# CATS-FAT-Battery-Interface.net
KiCad netlist of a schematic drawn in Altium Designer
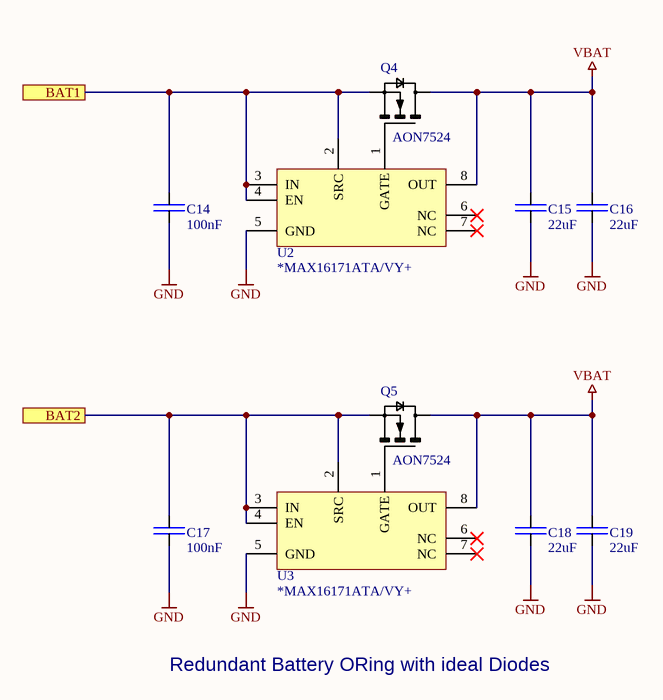
[diagram p0: CATS-FAT-Battery-Interface.SchDoc]

(export (version "E")
  (design (tool "Eeschema 10.0.6"))
  (components
    (comp (ref "C14")
      (value "100nF")
      (footprint "SMD Keramikkondensator 0603")
      (description "SMD Ceramic Capacitor E6")
      (libsource (lib "Ceramic Capacitors-E6") (part "E6 - 100nF"))
    )
    (comp (ref "C15")
      (value "22uF")
      (footprint "SMD Keramikkondensator 0805")
      (description "SMD Ceramic Capacitor E6")
      (libsource (lib "Ceramic Capacitors-E6") (part "E6 - 22uF"))
    )
    (comp (ref "C16")
      (value "22uF")
      (footprint "SMD Keramikkondensator 0805")
      (description "SMD Ceramic Capacitor E6")
      (libsource (lib "Ceramic Capacitors-E6") (part "E6 - 22uF"))
    )
    (comp (ref "C17")
      (value "100nF")
      (footprint "SMD Keramikkondensator 0603")
      (description "SMD Ceramic Capacitor E6")
      (libsource (lib "Ceramic Capacitors-E6") (part "E6 - 100nF"))
    )
    (comp (ref "C18")
      (value "22uF")
      (footprint "SMD Keramikkondensator 0805")
      (description "SMD Ceramic Capacitor E6")
      (libsource (lib "Ceramic Capacitors-E6") (part "E6 - 22uF"))
    )
    (comp (ref "C19")
      (value "22uF")
      (footprint "SMD Keramikkondensator 0805")
      (description "SMD Ceramic Capacitor E6")
      (libsource (lib "Ceramic Capacitors-E6") (part "E6 - 22uF"))
    )
    (comp (ref "Q4")
      (value "AON7524")
      (footprint "SMD MOSFET DFN 3x3 EP")
      (description "N-Channel 30V 25A (Ta), 28A (Tc) 3.1W (Ta), 32W (Tc) Surface Mount 8-DFN (3x3)")
      (libsource (lib "Electronic Switches") (part "AON7524"))
    )
    (comp (ref "Q5")
      (value "AON7524")
      (footprint "SMD MOSFET DFN 3x3 EP")
      (description "N-Channel 30V 25A (Ta), 28A (Tc) 3.1W (Ta), 32W (Tc) Surface Mount 8-DFN (3x3)")
      (libsource (lib "Electronic Switches") (part "AON7524"))
    )
    (comp (ref "U2")
      (value "*MAX16171ATA/VY+")
      (footprint "SMD IC TDFN-8")
      (description "OR Controller N+1 ORing Controller N-Channel 1:1 8-TDFN-CU (2x3)")
      (libsource (lib "Power Management") (part "MAX16171ATA/VY+"))
    )
    (comp (ref "U3")
      (value "*MAX16171ATA/VY+")
      (footprint "SMD IC TDFN-8")
      (description "OR Controller N+1 ORing Controller N-Channel 1:1 8-TDFN-CU (2x3)")
      (libsource (lib "Power Management") (part "MAX16171ATA/VY+"))
    )
  )
  (nets
    (net (code "1") (name "/BAT1") (class "Default")
      (node (ref "C14") (pin "2") (pinfunction "2_2") (pintype "passive"))
      (node (ref "Q4") (pin "S") (pinfunction "S_S") (pintype "passive"))
      (node (ref "U2") (pin "2") (pinfunction "SRC_2") (pintype "passive"))
      (node (ref "U2") (pin "3") (pinfunction "IN_3") (pintype "passive"))
      (node (ref "U2") (pin "4") (pinfunction "EN_4") (pintype "passive"))
    )
    (net (code "2") (name "/BAT2") (class "Default")
      (node (ref "C17") (pin "2") (pinfunction "2_2") (pintype "passive"))
      (node (ref "Q5") (pin "S") (pinfunction "S_S") (pintype "passive"))
      (node (ref "U3") (pin "2") (pinfunction "SRC_2") (pintype "passive"))
      (node (ref "U3") (pin "3") (pinfunction "IN_3") (pintype "passive"))
      (node (ref "U3") (pin "4") (pinfunction "EN_4") (pintype "passive"))
    )
    (net (code "3") (name "GND") (class "Default")
      (node (ref "C14") (pin "1") (pinfunction "1_1") (pintype "passive"))
      (node (ref "C15") (pin "1") (pinfunction "1_1") (pintype "passive"))
      (node (ref "C16") (pin "1") (pinfunction "1_1") (pintype "passive"))
      (node (ref "C17") (pin "1") (pinfunction "1_1") (pintype "passive"))
      (node (ref "C18") (pin "1") (pinfunction "1_1") (pintype "passive"))
      (node (ref "C19") (pin "1") (pinfunction "1_1") (pintype "passive"))
      (node (ref "U2") (pin "5") (pinfunction "GND_5") (pintype "passive"))
      (node (ref "U3") (pin "5") (pinfunction "GND_5") (pintype "passive"))
    )
    (net (code "4") (name "Net-(U2-GATE)") (class "Default")
      (node (ref "Q4") (pin "G") (pinfunction "G_G") (pintype "passive"))
      (node (ref "U2") (pin "1") (pinfunction "GATE_1") (pintype "passive"))
    )
    (net (code "5") (name "Net-(U3-GATE)") (class "Default")
      (node (ref "Q5") (pin "G") (pinfunction "G_G") (pintype "passive"))
      (node (ref "U3") (pin "1") (pinfunction "GATE_1") (pintype "passive"))
    )
    (net (code "6") (name "VBAT") (class "Default")
      (node (ref "C15") (pin "2") (pinfunction "2_2") (pintype "passive"))
      (node (ref "C16") (pin "2") (pinfunction "2_2") (pintype "passive"))
      (node (ref "C18") (pin "2") (pinfunction "2_2") (pintype "passive"))
      (node (ref "C19") (pin "2") (pinfunction "2_2") (pintype "passive"))
      (node (ref "Q4") (pin "D") (pinfunction "D_D") (pintype "passive"))
      (node (ref "Q5") (pin "D") (pinfunction "D_D") (pintype "passive"))
      (node (ref "U2") (pin "8") (pinfunction "OUT_8") (pintype "passive"))
      (node (ref "U3") (pin "8") (pinfunction "OUT_8") (pintype "passive"))
    )
    (net (code "7") (name "unconnected-(U2-NC-Pad6)") (class "Default")
      (node (ref "U2") (pin "6") (pinfunction "NC_6") (pintype "passive+no_connect"))
    )
    (net (code "8") (name "unconnected-(U2-NC-Pad7)") (class "Default")
      (node (ref "U2") (pin "7") (pinfunction "NC_7") (pintype "passive+no_connect"))
    )
    (net (code "9") (name "unconnected-(U3-NC-Pad6)") (class "Default")
      (node (ref "U3") (pin "6") (pinfunction "NC_6") (pintype "passive+no_connect"))
    )
    (net (code "10") (name "unconnected-(U3-NC-Pad7)") (class "Default")
      (node (ref "U3") (pin "7") (pinfunction "NC_7") (pintype "passive+no_connect"))
    )
  )
)
